# Power_Supply.net
KiCad netlist of a schematic drawn in Altium Designer
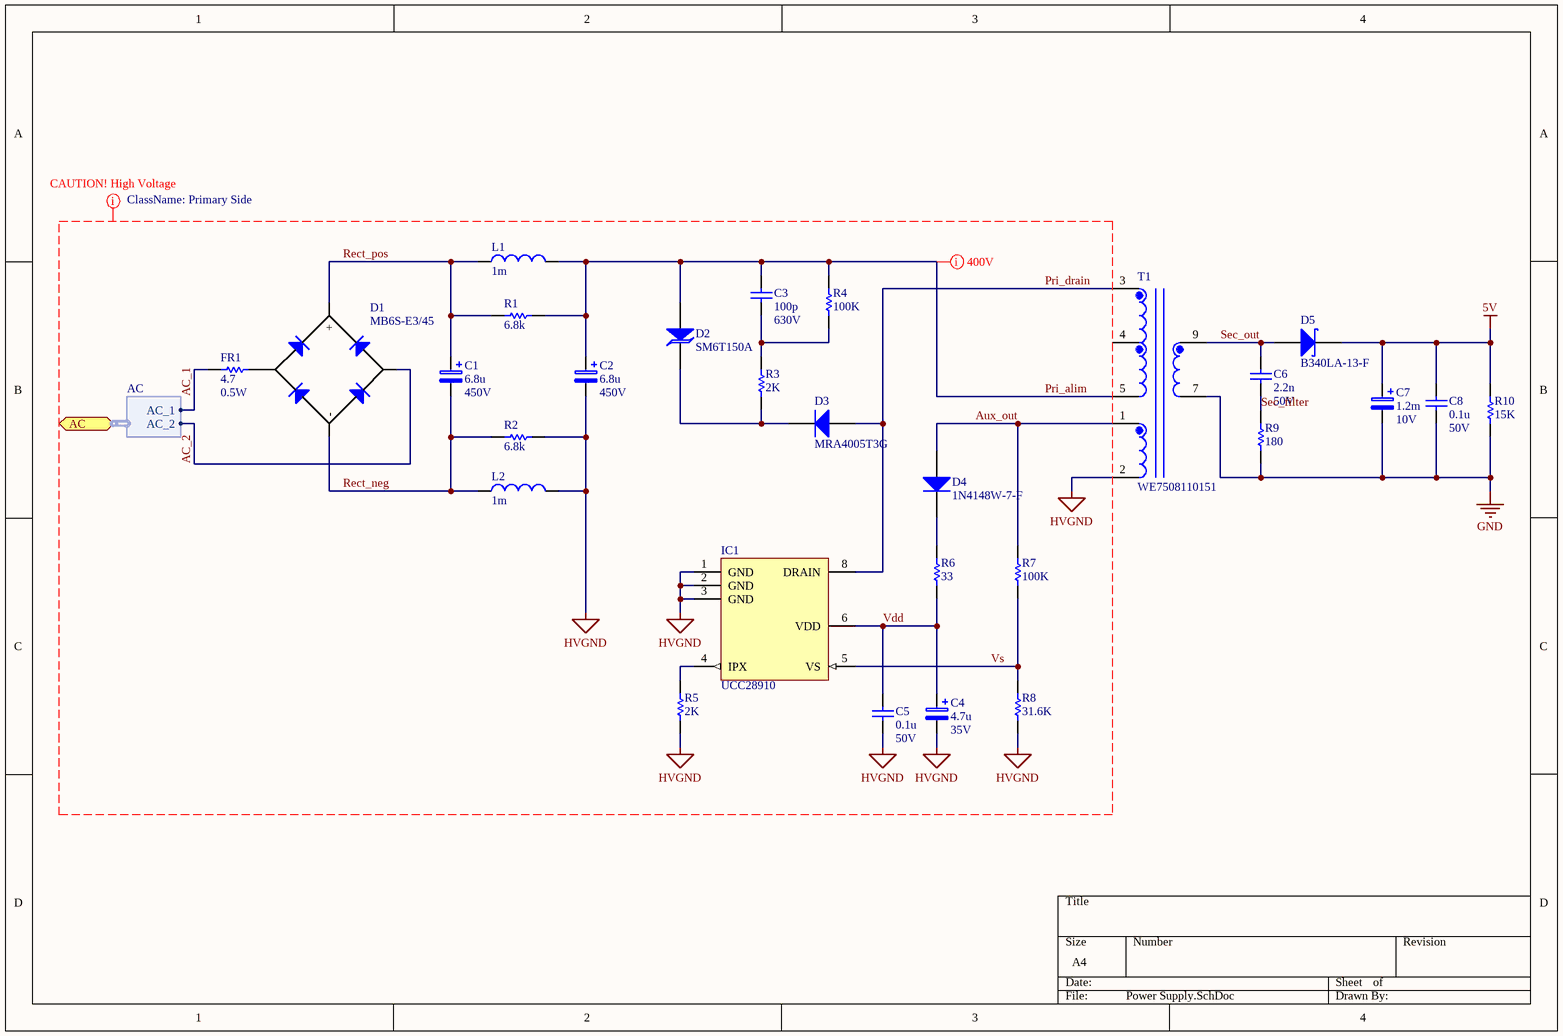
[diagram p0: Power Supply.SchDoc]

(export (version "E")
  (design (tool "Eeschema 10.0.6"))
  (components
    (comp (ref "C1")
      (value "6.8u")
      (footprint "CRADIAL-5mm-16mm")
      (description "Polarized Capacitor")
      (fields (field (name "RATED VOLTAGE") "450V"))
      (libsource (lib "Common Devices") (part "Pol Capacitor"))
    )
    (comp (ref "C2")
      (value "6.8u")
      (footprint "CRADIAL-5mm-16mm")
      (description "Polarized Capacitor")
      (fields (field (name "RATED VOLTAGE") "450V"))
      (libsource (lib "Common Devices") (part "Pol Capacitor"))
    )
    (comp (ref "C3")
      (value "100p")
      (footprint "C1206")
      (description "Capacitor")
      (fields (field (name "RATED VOLTAGE") "630V"))
      (libsource (lib "Common Devices") (part "Capacitor"))
    )
    (comp (ref "C4")
      (value "4.7u")
      (footprint "CAPAE5543X54N")
      (description "Polarized Capacitor")
      (fields (field (name "RATED VOLTAGE") "35V"))
      (libsource (lib "Common Devices") (part "Pol Capacitor"))
    )
    (comp (ref "C5")
      (value "0.1u")
      (footprint "C1206")
      (description "Capacitor")
      (fields (field (name "RATED VOLTAGE") "50V"))
      (libsource (lib "Common Devices") (part "Capacitor"))
    )
    (comp (ref "C6")
      (value "2.2n")
      (footprint "C1206")
      (description "Capacitor")
      (fields (field (name "RATED VOLTAGE") "50V"))
      (libsource (lib "Common Devices") (part "Capacitor"))
    )
    (comp (ref "C7")
      (value "1.2m")
      (footprint "CRADIAL-5mm-20mm")
      (description "Polarized Capacitor")
      (fields (field (name "RATED VOLTAGE") "10V"))
      (libsource (lib "Common Devices") (part "Pol Capacitor"))
    )
    (comp (ref "C8")
      (value "0.1u")
      (footprint "C1206")
      (description "Capacitor")
      (fields (field (name "RATED VOLTAGE") "50V"))
      (libsource (lib "Common Devices") (part "Capacitor"))
    )
    (comp (ref "D1")
      (value "MB6S-E3/45")
      (footprint "SOP250P670X290-4N")
      (description "Diode, Bridge Rectifier")
      (libsource (lib "Docking Station") (part "MB6S-E3/45"))
    )
    (comp (ref "D2")
      (value "SM6T150A")
      (footprint "SMB")
      (description "Diode, Transient Voltage Suppresor, 150V, 600W")
      (libsource (lib "Docking Station") (part "SM6T150A"))
    )
    (comp (ref "D3")
      (value "MRA4005T3G")
      (footprint "SMA")
      (description "Diode, Standard, 1A")
      (libsource (lib "Docking Station") (part "MRA4005T3G"))
    )
    (comp (ref "D4")
      (value "1N4148W-7-F")
      (footprint "SOD123")
      (description "Diode, Switch, 300mA, 100V")
      (libsource (lib "Docking Station") (part "1N4148W-7-F"))
    )
    (comp (ref "D5")
      (value "B340LA-13-F")
      (footprint "SMA")
      (description "Diode, Schottky, 40V, 3A")
      (libsource (lib "Docking Station") (part "B340LA-13-F"))
    )
    (comp (ref "FR1")
      (value "4.7")
      (footprint "RAXIAL-10mm-0.8mm")
      (description "Resistor, Fuse")
      (fields (field (name "POWER") "0.5W"))
      (libsource (lib "Common Devices") (part "Fuse Resistor"))
    )
    (comp (ref "IC1")
      (value "UCC28910")
      (footprint "SOIC127P600X175-7N")
      (description "700V Flyback Switcher with Constant-Voltage Constant-Current and Primary-side Control")
      (libsource (lib "Docking Station") (part "UCC28910"))
    )
    (comp (ref "L1")
      (value "1m")
      (footprint "INDUCTOR-5MM")
      (description "Inductor")
      (libsource (lib "Common Devices") (part "Inductor"))
    )
    (comp (ref "L2")
      (value "1m")
      (footprint "INDUCTOR-5MM")
      (description "Inductor")
      (libsource (lib "Common Devices") (part "Inductor"))
    )
    (comp (ref "R1")
      (value "6.8k")
      (footprint "R1206")
      (description "Resistor")
      (libsource (lib "Common Devices") (part "Resistor"))
    )
    (comp (ref "R2")
      (value "6.8k")
      (footprint "R1206")
      (description "Resistor")
      (libsource (lib "Common Devices") (part "Resistor"))
    )
    (comp (ref "R3")
      (value "2K")
      (footprint "R1206")
      (description "Resistor")
      (libsource (lib "Common Devices") (part "Resistor"))
    )
    (comp (ref "R4")
      (value "100K")
      (footprint "R1206")
      (description "Resistor")
      (libsource (lib "Common Devices") (part "Resistor"))
    )
    (comp (ref "R5")
      (value "2K")
      (footprint "R1206")
      (description "Resistor")
      (libsource (lib "Common Devices") (part "Resistor"))
    )
    (comp (ref "R6")
      (value "33")
      (footprint "R1206")
      (description "Resistor")
      (libsource (lib "Common Devices") (part "Resistor"))
    )
    (comp (ref "R7")
      (value "100K")
      (footprint "R1206")
      (description "Resistor")
      (libsource (lib "Common Devices") (part "Resistor"))
    )
    (comp (ref "R8")
      (value "31.6K")
      (footprint "R1206")
      (description "Resistor")
      (libsource (lib "Common Devices") (part "Resistor"))
    )
    (comp (ref "R9")
      (value "180")
      (footprint "R1206")
      (description "Resistor")
      (libsource (lib "Common Devices") (part "Resistor"))
    )
    (comp (ref "R10")
      (value "15K")
      (footprint "R1206")
      (description "Resistor")
      (libsource (lib "Common Devices") (part "Resistor"))
    )
    (comp (ref "T1")
      (value "WE7508110151")
      (footprint "WE7508110151")
      (description "Transformer, Flyback")
      (libsource (lib "Docking Station") (part "WE7508110151"))
    )
  )
  (nets
    (net (code "2") (name "/AC_1") (class "Default")
      (node (ref "FR1") (pin "1") (pinfunction "1_1") (pintype "passive"))
    )
    (net (code "3") (name "/AC_2") (class "Default")
      (node (ref "D1") (pin "2") (pinfunction "AC_2") (pintype "passive"))
    )
    (net (code "4") (name "/Aux_out") (class "Default")
      (node (ref "D4") (pin "1") (pinfunction "A_1") (pintype "passive"))
      (node (ref "R7") (pin "2") (pinfunction "2_2") (pintype "passive"))
      (node (ref "T1") (pin "1") (pinfunction "Aux1_1") (pintype "passive"))
    )
    (net (code "5") (name "/Pri_alim") (class "Default")
      (node (ref "C2") (pin "1") (pinfunction "1_1") (pintype "passive"))
      (node (ref "C3") (pin "2") (pinfunction "2_2") (pintype "passive"))
      (node (ref "D2") (pin "1") (pinfunction "A_1") (pintype "passive"))
      (node (ref "L1") (pin "2") (pinfunction "2_2") (pintype "passive"))
      (node (ref "R1") (pin "2") (pinfunction "2_2") (pintype "passive"))
      (node (ref "R4") (pin "2") (pinfunction "2_2") (pintype "passive"))
      (node (ref "T1") (pin "5") (pinfunction "Pri3_5") (pintype "passive"))
    )
    (net (code "6") (name "/Pri_drain") (class "Default")
      (node (ref "D3") (pin "1") (pinfunction "A_1") (pintype "passive"))
      (node (ref "IC1") (pin "8") (pinfunction "DRAIN_8") (pintype "passive"))
      (node (ref "T1") (pin "3") (pinfunction "Pri1_3") (pintype "passive"))
    )
    (net (code "7") (name "/Rect_neg") (class "Default")
      (node (ref "C1") (pin "2") (pinfunction "2_2") (pintype "passive"))
      (node (ref "D1") (pin "4") (pinfunction "-_4") (pintype "passive"))
      (node (ref "L2") (pin "1") (pinfunction "1_1") (pintype "passive"))
      (node (ref "R2") (pin "1") (pinfunction "1_1") (pintype "passive"))
    )
    (net (code "8") (name "/Rect_pos") (class "Default")
      (node (ref "C1") (pin "1") (pinfunction "1_1") (pintype "passive"))
      (node (ref "D1") (pin "3") (pinfunction "+_3") (pintype "passive"))
      (node (ref "L1") (pin "1") (pinfunction "1_1") (pintype "passive"))
      (node (ref "R1") (pin "1") (pinfunction "1_1") (pintype "passive"))
    )
    (net (code "9") (name "/Sec_filter") (class "Default")
      (node (ref "C6") (pin "1") (pinfunction "1_1") (pintype "passive"))
      (node (ref "R9") (pin "2") (pinfunction "2_2") (pintype "passive"))
    )
    (net (code "10") (name "/Sec_out") (class "Default")
      (node (ref "C6") (pin "2") (pinfunction "2_2") (pintype "passive"))
      (node (ref "D5") (pin "1") (pinfunction "A_1") (pintype "passive"))
      (node (ref "T1") (pin "9") (pinfunction "Sec1_9") (pintype "passive"))
    )
    (net (code "11") (name "/Vdd") (class "Default")
      (node (ref "C4") (pin "1") (pinfunction "1_1") (pintype "passive"))
      (node (ref "C5") (pin "2") (pinfunction "2_2") (pintype "passive"))
      (node (ref "IC1") (pin "6") (pinfunction "VDD_6") (pintype "power_in"))
      (node (ref "R6") (pin "1") (pinfunction "1_1") (pintype "passive"))
    )
    (net (code "12") (name "/Vs") (class "Default")
      (node (ref "IC1") (pin "5") (pinfunction "VS_5") (pintype "input"))
      (node (ref "R7") (pin "1") (pinfunction "1_1") (pintype "passive"))
      (node (ref "R8") (pin "2") (pinfunction "2_2") (pintype "passive"))
    )
    (net (code "14") (name "5V") (class "Default")
      (node (ref "C7") (pin "1") (pinfunction "1_1") (pintype "passive"))
      (node (ref "C8") (pin "2") (pinfunction "2_2") (pintype "passive"))
      (node (ref "D5") (pin "2") (pinfunction "K_2") (pintype "passive"))
      (node (ref "R10") (pin "2") (pinfunction "2_2") (pintype "passive"))
    )
    (net (code "15") (name "GND") (class "Default")
      (node (ref "C7") (pin "2") (pinfunction "2_2") (pintype "passive"))
      (node (ref "C8") (pin "1") (pinfunction "1_1") (pintype "passive"))
      (node (ref "R10") (pin "1") (pinfunction "1_1") (pintype "passive"))
      (node (ref "R9") (pin "1") (pinfunction "1_1") (pintype "passive"))
      (node (ref "T1") (pin "7") (pinfunction "Sec2_7") (pintype "passive"))
    )
    (net (code "16") (name "HVGND") (class "Default")
      (node (ref "C2") (pin "2") (pinfunction "2_2") (pintype "passive"))
      (node (ref "C4") (pin "2") (pinfunction "2_2") (pintype "passive"))
      (node (ref "C5") (pin "1") (pinfunction "1_1") (pintype "passive"))
      (node (ref "IC1") (pin "1") (pinfunction "GND_1") (pintype "power_in"))
      (node (ref "IC1") (pin "2") (pinfunction "GND_2") (pintype "power_in"))
      (node (ref "IC1") (pin "3") (pinfunction "GND_3") (pintype "power_in"))
      (node (ref "L2") (pin "2") (pinfunction "2_2") (pintype "passive"))
      (node (ref "R2") (pin "2") (pinfunction "2_2") (pintype "passive"))
      (node (ref "R5") (pin "1") (pinfunction "1_1") (pintype "passive"))
      (node (ref "R8") (pin "1") (pinfunction "1_1") (pintype "passive"))
      (node (ref "T1") (pin "2") (pinfunction "Aux2_2") (pintype "passive"))
    )
    (net (code "17") (name "Net-(C3-Pad1)") (class "Default")
      (node (ref "C3") (pin "1") (pinfunction "1_1") (pintype "passive"))
      (node (ref "R3") (pin "2") (pinfunction "2_2") (pintype "passive"))
      (node (ref "R4") (pin "1") (pinfunction "1_1") (pintype "passive"))
    )
    (net (code "18") (name "Net-(D1-AC-Pad1)") (class "Default")
      (node (ref "D1") (pin "1") (pinfunction "AC_1") (pintype "passive"))
      (node (ref "FR1") (pin "2") (pinfunction "2_2") (pintype "passive"))
    )
    (net (code "19") (name "Net-(D2-K)") (class "Default")
      (node (ref "D2") (pin "2") (pinfunction "K_2") (pintype "passive"))
      (node (ref "D3") (pin "2") (pinfunction "K_2") (pintype "passive"))
      (node (ref "R3") (pin "1") (pinfunction "1_1") (pintype "passive"))
    )
    (net (code "20") (name "Net-(D4-K)") (class "Default")
      (node (ref "D4") (pin "2") (pinfunction "K_2") (pintype "passive"))
      (node (ref "R6") (pin "2") (pinfunction "2_2") (pintype "passive"))
    )
    (net (code "21") (name "Net-(IC1-IPX)") (class "Default")
      (node (ref "IC1") (pin "4") (pinfunction "IPX_4") (pintype "output"))
      (node (ref "R5") (pin "2") (pinfunction "2_2") (pintype "passive"))
    )
    (net (code "22") (name "unconnected-(T1-Pri2-Pad4)") (class "Default")
      (node (ref "T1") (pin "4") (pinfunction "Pri2_4") (pintype "passive"))
    )
  )
)
